# Microcontroller.net
KiCad netlist of a schematic drawn in Altium Designer
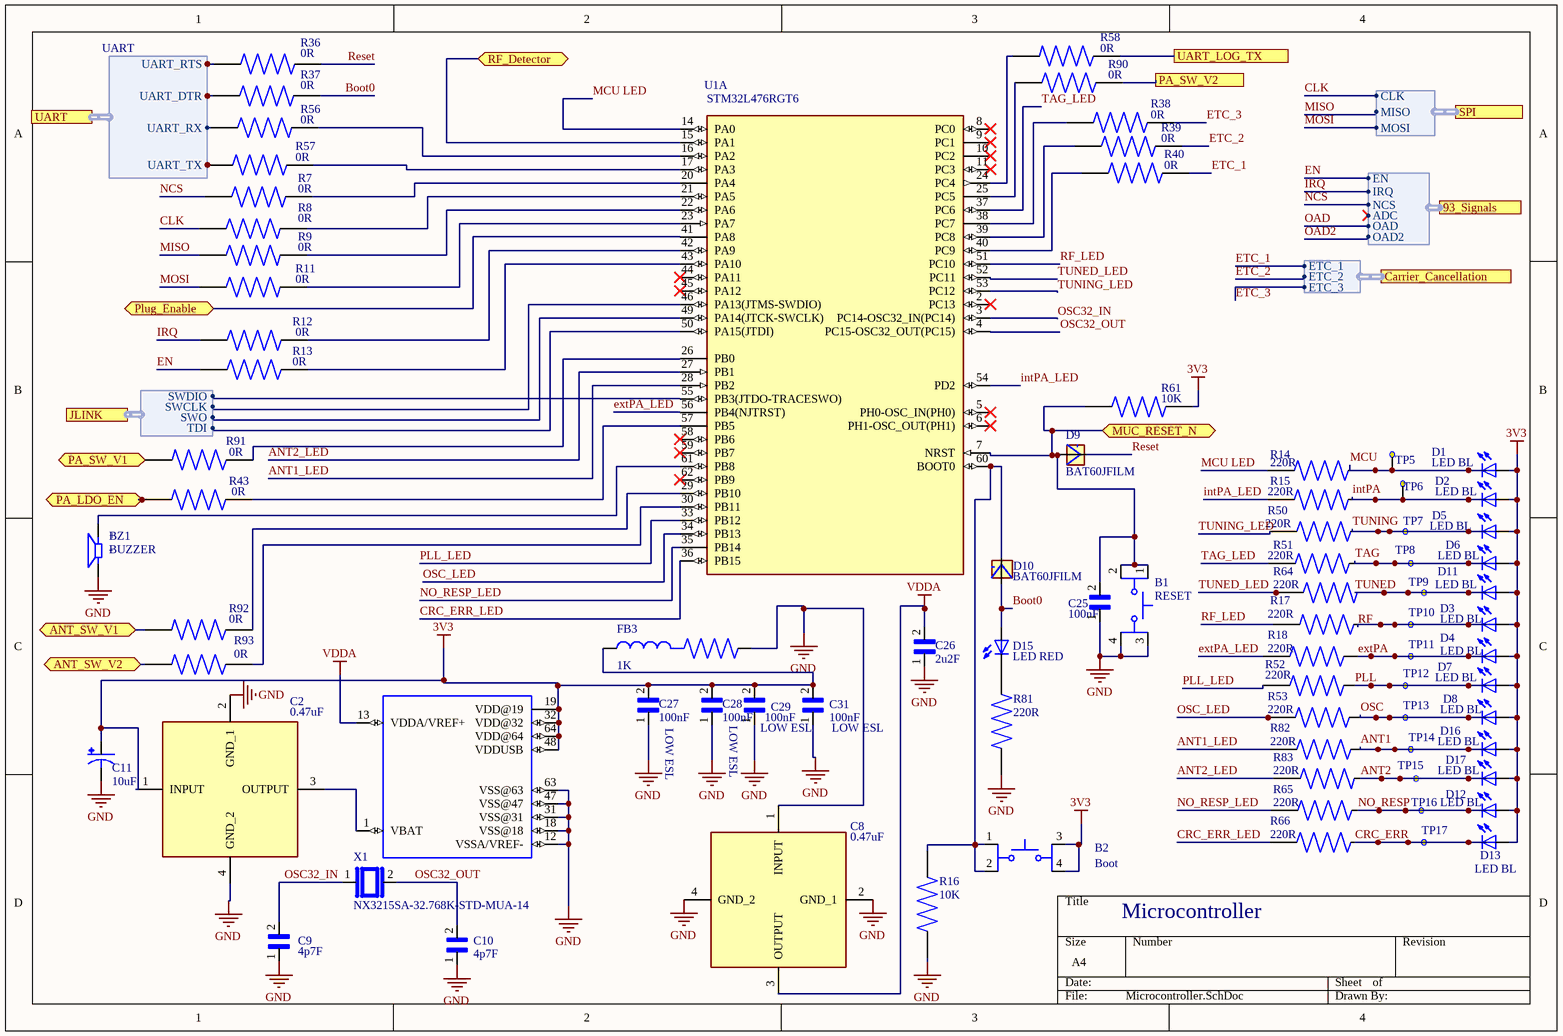
[diagram p0: Microcontroller.SchDoc]

(export (version "E")
  (design (tool "Eeschema 10.0.6"))
  (components
    (comp (ref "B1")
      (value "RESET")
      (footprint "SW_TL3301AF160QG")
      (description "Tactile Switch SPST-NO Top Actuated Surface Mount")
      (fields (field (name "MP") "TL3301AF160QG") (field (name "MF") "E-Switch"))
      (libsource (lib "TL3301AF160QG") (part "TL3301AF160QG"))
    )
    (comp (ref "B2")
      (value "Boot")
      (footprint "SW_TL3301AF160QG")
      (description "Tactile Switch SPST-NO Top Actuated Surface Mount")
      (fields (field (name "MP") "TL3301AF160QG") (field (name "MF") "E-Switch"))
      (libsource (lib "TL3301AF160QG") (part "TL3301AF160QG"))
    )
    (comp (ref "BZ1")
      (value "BUZZER")
      (footprint "SPKR_PKMCS0909E4000-R1")
      (description "Buzzers Transducer, Externally Driven Piezo 1.5V 4kHz 65dB @ 1.5V, 10cm Surface Mount Solder Pads")
      (fields (field (name "DIGI-KEY_PART_NUMBER") "490-9647-1-ND") (field (name "MP") "PKMCS0909E4000-R1"))
      (libsource (lib "PKMCS0909E4000-R1") (part "PKMCS0909E4000-R1"))
    )
    (comp (ref "C2")
      (value "0.47uF")
      (footprint "SamacSys:NFM18CC101R1C3D")
      (description "Capacitor")
      (fields
        (field (name "MANUFACTURER_PART_NUMBER") "NFM18PS474R0J3D")
        (field (name "MOUSER PART NUMBER") "81-NFM18PS474R0J3D")
      )
      (libsource (lib "") (part "NFM18PS474R0J3D_1"))
    )
    (comp (ref "C8")
      (value "0.47uF")
      (footprint "SamacSys:NFM18CC101R1C3D")
      (description "Capacitor")
      (fields
        (field (name "MANUFACTURER_PART_NUMBER") "NFM18PS474R0J3D")
        (field (name "MOUSER PART NUMBER") "81-NFM18PS474R0J3D")
      )
      (libsource (lib "*") (part "NFM18PS474R0J3D"))
    )
    (comp (ref "C9")
      (value "4p7F")
      (footprint "CAPC1005X55N")
      (description "Cap Ceramic 4.7pF 100V C0G 0.25pF SMD 0402 125Â°C Paper T/R")
      (fields (field (name "MP") "GRM1555C2A4R7CA01D"))
      (libsource (lib "GRM1555C2A4R7CA01D") (part "GRM1555C2A4R7CA01D"))
    )
    (comp (ref "C10")
      (value "4p7F")
      (footprint "CAPC1005X55N")
      (description "Cap Ceramic 4.7pF 100V C0G 0.25pF SMD 0402 125Â°C Paper T/R")
      (fields (field (name "MP") "GRM1555C2A4R7CA01D"))
      (libsource (lib "GRM1555C2A4R7CA01D") (part "GRM1555C2A4R7CA01D"))
    )
    (comp (ref "C11")
      (value "10uF")
      (footprint "2917(POL)")
      (description "10 ÂµF 16 V Aluminum - Polymer Capacitors 2917 (7343 Metric) 60mOhm 1000 Hrs @ 105Â°C")
      (fields (field (name "MF") "Murata Electronics") (field (name "MP") "ECASD41C106M060K00"))
      (libsource (lib "ECASD41C106M060K00") (part "ECASD41C106M060K00"))
    )
    (comp (ref "C25")
      (value "100nF")
      (footprint "CAPC1005X55N")
      (description "SMD Capacitor X7R_EIA_ with Capacitance: 0.10uF Tol. 10%. Rated Voltage: 16Vdc")
      (fields (field (name "MF") "Murata") (field (name "MP") "GRM155R71C104KA88D"))
      (libsource (lib "GRM155R71C104KA88D") (part "GRM155R71C104KA88D"))
    )
    (comp (ref "C26")
      (value "2u2F")
      (footprint "CAPC0603X35N")
      (description "SMD Capacitor X5R(EIA) with Capacitance: 2.2uF Tol. 20%. Rated Voltage: 6.3Vdc")
      (fields (field (name "MP") "GRM033R60J225ME15D"))
      (libsource (lib "GRM033R60J225ME15D") (part "GRM033R60J225ME15D"))
    )
    (comp (ref "C27")
      (value "100nF")
      (footprint "CAPC0510X35N")
      (description "SMD Capacitor X6S(EIA) with Capacitance: 0.10uF Tol. 20%. Rated Voltage: 6.3Vdc")
      (fields (field (name "MF") "Murata") (field (name "MP") "LLL153C80J104ME01E"))
      (libsource (lib "LLL153C80J104ME01E") (part "LLL153C80J104ME01E"))
    )
    (comp (ref "C28")
      (value "100nF")
      (footprint "CAPC0510X35N")
      (description "SMD Capacitor X6S(EIA) with Capacitance: 0.10uF Tol. 20%. Rated Voltage: 6.3Vdc")
      (fields (field (name "MF") "Murata") (field (name "MP") "LLL153C80J104ME01E"))
      (libsource (lib "LLL153C80J104ME01E") (part "LLL153C80J104ME01E"))
    )
    (comp (ref "C29")
      (value "100nF")
      (footprint "CAPC0510X35N")
      (description "SMD Capacitor X6S(EIA) with Capacitance: 0.10uF Tol. 20%. Rated Voltage: 6.3Vdc")
      (fields (field (name "MF") "Murata") (field (name "MP") "LLL153C80J104ME01E"))
      (libsource (lib "LLL153C80J104ME01E") (part "LLL153C80J104ME01E"))
    )
    (comp (ref "C31")
      (value "100nF")
      (footprint "CAPC0510X35N")
      (description "SMD Capacitor X6S(EIA) with Capacitance: 0.10uF Tol. 20%. Rated Voltage: 6.3Vdc")
      (fields (field (name "MF") "Murata") (field (name "MP") "LLL153C80J104ME01E"))
      (libsource (lib "LLL153C80J104ME01E") (part "LLL153C80J104ME01E"))
    )
    (comp (ref "D1")
      (value "LED BL")
      (footprint "LED_0402")
      (description "Blue 472nm LED Indication - Discrete 2.9V 0402 (1005 Metric)")
      (fields (field (name "MF") "Panasonic Electronic") (field (name "MP") "LNJ947W8CRA"))
      (libsource (lib "LNJ947W8CRA") (part "LNJ947W8CRA"))
    )
    (comp (ref "D2")
      (value "LED BL")
      (footprint "LED_0402")
      (description "Blue 472nm LED Indication - Discrete 2.9V 0402 (1005 Metric)")
      (fields (field (name "MF") "Panasonic Electronic") (field (name "MP") "LNJ947W8CRA"))
      (libsource (lib "LNJ947W8CRA") (part "LNJ947W8CRA"))
    )
    (comp (ref "D3")
      (value "LED BL")
      (footprint "LED_0402")
      (description "Blue 472nm LED Indication - Discrete 2.9V 0402 (1005 Metric)")
      (fields (field (name "MF") "Panasonic Electronic") (field (name "MP") "LNJ947W8CRA"))
      (libsource (lib "LNJ947W8CRA") (part "LNJ947W8CRA"))
    )
    (comp (ref "D4")
      (value "LED BL")
      (footprint "LED_0402")
      (description "Blue 472nm LED Indication - Discrete 2.9V 0402 (1005 Metric)")
      (fields (field (name "MF") "Panasonic Electronic") (field (name "MP") "LNJ947W8CRA"))
      (libsource (lib "LNJ947W8CRA") (part "LNJ947W8CRA"))
    )
    (comp (ref "D5")
      (value "LED BL")
      (footprint "LED_0402")
      (description "Blue 472nm LED Indication - Discrete 2.9V 0402 (1005 Metric)")
      (fields (field (name "MF") "Panasonic Electronic") (field (name "MP") "LNJ947W8CRA"))
      (libsource (lib "LNJ947W8CRA") (part "LNJ947W8CRA"))
    )
    (comp (ref "D6")
      (value "LED BL")
      (footprint "LED_0402")
      (description "Blue 472nm LED Indication - Discrete 2.9V 0402 (1005 Metric)")
      (fields (field (name "MF") "Panasonic Electronic") (field (name "MP") "LNJ947W8CRA"))
      (libsource (lib "LNJ947W8CRA") (part "LNJ947W8CRA"))
    )
    (comp (ref "D7")
      (value "LED BL")
      (footprint "LED_0402")
      (description "Blue 472nm LED Indication - Discrete 2.9V 0402 (1005 Metric)")
      (fields (field (name "MF") "Panasonic Electronic") (field (name "MP") "LNJ947W8CRA"))
      (libsource (lib "LNJ947W8CRA") (part "LNJ947W8CRA"))
    )
    (comp (ref "D8")
      (value "LED BL")
      (footprint "LED_0402")
      (description "Blue 472nm LED Indication - Discrete 2.9V 0402 (1005 Metric)")
      (fields (field (name "MF") "Panasonic Electronic") (field (name "MP") "LNJ947W8CRA"))
      (libsource (lib "LNJ947W8CRA") (part "LNJ947W8CRA"))
    )
    (comp (ref "D9")
      (value "BAT60JFILM")
      (footprint "SOD323")
      (description "Diode Schottky 10 V 3A (DC) Surface Mount SOD-323")
      (fields (field (name "MF") "STMicroelectronics"))
      (libsource (lib "") (part "BAT60JFILM_1"))
    )
    (comp (ref "D10")
      (value "BAT60JFILM")
      (footprint "SOD323")
      (description "Diode Schottky 10 V 3A (DC) Surface Mount SOD-323")
      (fields (field (name "MF") "STMicroelectronics"))
      (libsource (lib "BAT60JFILM") (part "BAT60JFILM"))
    )
    (comp (ref "D11")
      (value "LED BL")
      (footprint "LED_0402")
      (description "Blue 472nm LED Indication - Discrete 2.9V 0402 (1005 Metric)")
      (fields (field (name "MF") "Panasonic Electronic") (field (name "MP") "LNJ947W8CRA"))
      (libsource (lib "LNJ947W8CRA") (part "LNJ947W8CRA"))
    )
    (comp (ref "D12")
      (value "LED BL")
      (footprint "LED_0402")
      (description "Blue 472nm LED Indication - Discrete 2.9V 0402 (1005 Metric)")
      (fields (field (name "MF") "Panasonic Electronic") (field (name "MP") "LNJ947W8CRA"))
      (libsource (lib "LNJ947W8CRA") (part "LNJ947W8CRA"))
    )
    (comp (ref "D13")
      (value "LED BL")
      (footprint "LED_0402")
      (description "Blue 472nm LED Indication - Discrete 2.9V 0402 (1005 Metric)")
      (fields (field (name "MF") "Panasonic Electronic") (field (name "MP") "LNJ947W8CRA"))
      (libsource (lib "LNJ947W8CRA") (part "LNJ947W8CRA"))
    )
    (comp (ref "D15")
      (value "LED RED")
      (footprint "LED_0402")
      (description "Red 630nm LED Indication - Discrete 1.95V 0402 (1005 Metric)")
      (fields (field (name "MF") "Panasonic Electronic") (field (name "MP") "LNJ247W82RA"))
      (libsource (lib "LNJ247W82RA") (part "LNJ247W82RA"))
    )
    (comp (ref "D16")
      (value "LED BL")
      (footprint "LED_0402")
      (description "Blue 472nm LED Indication - Discrete 2.9V 0402 (1005 Metric)")
      (fields (field (name "MF") "Panasonic Electronic") (field (name "MP") "LNJ947W8CRA"))
      (libsource (lib "LNJ947W8CRA") (part "LNJ947W8CRA"))
    )
    (comp (ref "D17")
      (value "LED BL")
      (footprint "LED_0402")
      (description "Blue 472nm LED Indication - Discrete 2.9V 0402 (1005 Metric)")
      (fields (field (name "MF") "Panasonic Electronic") (field (name "MP") "LNJ947W8CRA"))
      (libsource (lib "LNJ947W8CRA") (part "LNJ947W8CRA"))
    )
    (comp (ref "FB3")
      (value "1K")
      (footprint "BEADC1005X55N")
      (description "1 kOhms @ 100MHz 1 Signal Line Ferrite Bead 0402 _1005 Metric_ 250mA 1.1Ohm")
      (fields (field (name "MF") "Murata") (field (name "DIGI-KEY_PART_NUMBER") "490-3999-1-ND"))
      (libsource (lib "BLM15HG102SN1D") (part "BLM15HG102SN1D"))
    )
    (comp (ref "R7")
      (value "0R")
      (footprint "RESC1005X37N")
      (fields (field (name "MF") "{'manufacturer': u'YAGEO'}") (field (name "MP") "RC0402JR-070RL"))
      (libsource (lib "RC0402JR-070RL") (part "RC0402JR-070RL"))
    )
    (comp (ref "R8")
      (value "0R")
      (footprint "RESC1005X37N")
      (fields (field (name "MF") "{'manufacturer': u'YAGEO'}") (field (name "MP") "RC0402JR-070RL"))
      (libsource (lib "RC0402JR-070RL") (part "RC0402JR-070RL"))
    )
    (comp (ref "R9")
      (value "0R")
      (footprint "RESC1005X37N")
      (fields (field (name "MF") "{'manufacturer': u'YAGEO'}") (field (name "MP") "RC0402JR-070RL"))
      (libsource (lib "RC0402JR-070RL") (part "RC0402JR-070RL"))
    )
    (comp (ref "R11")
      (value "0R")
      (footprint "RESC1005X37N")
      (fields (field (name "MF") "{'manufacturer': u'YAGEO'}") (field (name "MP") "RC0402JR-070RL"))
      (libsource (lib "RC0402JR-070RL") (part "RC0402JR-070RL"))
    )
    (comp (ref "R12")
      (value "0R")
      (footprint "RESC1005X37N")
      (fields (field (name "MF") "{'manufacturer': u'YAGEO'}") (field (name "MP") "RC0402JR-070RL"))
      (libsource (lib "RC0402JR-070RL") (part "RC0402JR-070RL"))
    )
    (comp (ref "R13")
      (value "0R")
      (footprint "RESC1005X37N")
      (fields (field (name "MF") "{'manufacturer': u'YAGEO'}") (field (name "MP") "RC0402JR-070RL"))
      (libsource (lib "RC0402JR-070RL") (part "RC0402JR-070RL"))
    )
    (comp (ref "R14")
      (value "220R")
      (footprint "RESC1005X40N")
      (description "220 Ohms ±5% 0.063W, 1/16W Chip Resistor 0402 (1005 Metric) Moisture Resistant Thick Film")
      (fields (field (name "MF") "Yageo") (field (name "MP") "RC0402JR-07220RL"))
      (libsource (lib "RC0402JR-07220RL") (part "RC0402JR-07220RL"))
    )
    (comp (ref "R15")
      (value "220R")
      (footprint "RESC1005X40N")
      (description "220 Ohms ±5% 0.063W, 1/16W Chip Resistor 0402 (1005 Metric) Moisture Resistant Thick Film")
      (fields (field (name "MF") "Yageo") (field (name "MP") "RC0402JR-07220RL"))
      (libsource (lib "RC0402JR-07220RL") (part "RC0402JR-07220RL"))
    )
    (comp (ref "R16")
      (value "10K")
      (footprint "RESC1005X40N")
      (description "10 kOhms Â±1% 0.063W, 1/16W Chip Resistor 0402 (1005 Metric) Moisture Resistant Thick Film")
      (fields (field (name "MF") "Yageo") (field (name "MP") "RC0402FR-0710KL"))
      (libsource (lib "RC0402FR-0710KL") (part "RC0402FR-0710KL"))
    )
    (comp (ref "R17")
      (value "220R")
      (footprint "RESC1005X40N")
      (description "220 Ohms ±5% 0.063W, 1/16W Chip Resistor 0402 (1005 Metric) Moisture Resistant Thick Film")
      (fields (field (name "MF") "Yageo") (field (name "MP") "RC0402JR-07220RL"))
      (libsource (lib "RC0402JR-07220RL") (part "RC0402JR-07220RL"))
    )
    (comp (ref "R18")
      (value "220R")
      (footprint "RESC1005X40N")
      (description "220 Ohms ±5% 0.063W, 1/16W Chip Resistor 0402 (1005 Metric) Moisture Resistant Thick Film")
      (fields (field (name "MF") "Yageo") (field (name "MP") "RC0402JR-07220RL"))
      (libsource (lib "RC0402JR-07220RL") (part "RC0402JR-07220RL"))
    )
    (comp (ref "R36")
      (value "0R")
      (footprint "RESC1005X37N")
      (fields (field (name "MF") "{'manufacturer': u'YAGEO'}") (field (name "MP") "RC0402JR-070RL"))
      (libsource (lib "RC0402JR-070RL") (part "RC0402JR-070RL"))
    )
    (comp (ref "R37")
      (value "0R")
      (footprint "RESC1005X37N")
      (fields (field (name "MF") "{'manufacturer': u'YAGEO'}") (field (name "MP") "RC0402JR-070RL"))
      (libsource (lib "RC0402JR-070RL") (part "RC0402JR-070RL"))
    )
    (comp (ref "R38")
      (value "0R")
      (footprint "RESC1005X37N")
      (fields (field (name "MF") "{'manufacturer': u'YAGEO'}") (field (name "MP") "RC0402JR-070RL"))
      (libsource (lib "RC0402JR-070RL") (part "RC0402JR-070RL"))
    )
    (comp (ref "R39")
      (value "0R")
      (footprint "RESC1005X37N")
      (fields (field (name "MF") "{'manufacturer': u'YAGEO'}") (field (name "MP") "RC0402JR-070RL"))
      (libsource (lib "RC0402JR-070RL") (part "RC0402JR-070RL"))
    )
    (comp (ref "R40")
      (value "0R")
      (footprint "RESC1005X37N")
      (fields (field (name "MF") "{'manufacturer': u'YAGEO'}") (field (name "MP") "RC0402JR-070RL"))
      (libsource (lib "RC0402JR-070RL") (part "RC0402JR-070RL"))
    )
    (comp (ref "R43")
      (value "0R")
      (footprint "RESC1005X37N")
      (fields (field (name "MF") "{'manufacturer': u'YAGEO'}") (field (name "MP") "RC0402JR-070RL"))
      (libsource (lib "RC0402JR-070RL") (part "RC0402JR-070RL"))
    )
    (comp (ref "R50")
      (value "220R")
      (footprint "RESC1005X40N")
      (description "220 Ohms ±5% 0.063W, 1/16W Chip Resistor 0402 (1005 Metric) Moisture Resistant Thick Film")
      (fields (field (name "MF") "Yageo") (field (name "MP") "RC0402JR-07220RL"))
      (libsource (lib "RC0402JR-07220RL") (part "RC0402JR-07220RL"))
    )
    (comp (ref "R51")
      (value "220R")
      (footprint "RESC1005X40N")
      (description "220 Ohms ±5% 0.063W, 1/16W Chip Resistor 0402 (1005 Metric) Moisture Resistant Thick Film")
      (fields (field (name "MF") "Yageo") (field (name "MP") "RC0402JR-07220RL"))
      (libsource (lib "RC0402JR-07220RL") (part "RC0402JR-07220RL"))
    )
    (comp (ref "R52")
      (value "220R")
      (footprint "RESC1005X40N")
      (description "220 Ohms ±5% 0.063W, 1/16W Chip Resistor 0402 (1005 Metric) Moisture Resistant Thick Film")
      (fields (field (name "MF") "Yageo") (field (name "MP") "RC0402JR-07220RL"))
      (libsource (lib "RC0402JR-07220RL") (part "RC0402JR-07220RL"))
    )
    (comp (ref "R53")
      (value "220R")
      (footprint "RESC1005X40N")
      (description "220 Ohms ±5% 0.063W, 1/16W Chip Resistor 0402 (1005 Metric) Moisture Resistant Thick Film")
      (fields (field (name "MF") "Yageo") (field (name "MP") "RC0402JR-07220RL"))
      (libsource (lib "RC0402JR-07220RL") (part "RC0402JR-07220RL"))
    )
    (comp (ref "R56")
      (value "0R")
      (footprint "RESC1005X37N")
      (fields (field (name "MF") "{'manufacturer': u'YAGEO'}") (field (name "MP") "RC0402JR-070RL"))
      (libsource (lib "RC0402JR-070RL") (part "RC0402JR-070RL"))
    )
    (comp (ref "R57")
      (value "0R")
      (footprint "RESC1005X37N")
      (fields (field (name "MF") "{'manufacturer': u'YAGEO'}") (field (name "MP") "RC0402JR-070RL"))
      (libsource (lib "RC0402JR-070RL") (part "RC0402JR-070RL"))
    )
    (comp (ref "R58")
      (value "0R")
      (footprint "RESC1005X37N")
      (fields (field (name "MF") "{'manufacturer': u'YAGEO'}") (field (name "MP") "RC0402JR-070RL"))
      (libsource (lib "RC0402JR-070RL") (part "RC0402JR-070RL"))
    )
    (comp (ref "R61")
      (value "10K")
      (footprint "RESC1005X40N")
      (description "10 kOhms Â±1% 0.063W, 1/16W Chip Resistor 0402 (1005 Metric) Moisture Resistant Thick Film")
      (fields (field (name "MF") "Yageo") (field (name "MP") "RC0402FR-0710KL"))
      (libsource (lib "RC0402FR-0710KL") (part "RC0402FR-0710KL"))
    )
    (comp (ref "R64")
      (value "220R")
      (footprint "RESC1005X40N")
      (description "220 Ohms ±5% 0.063W, 1/16W Chip Resistor 0402 (1005 Metric) Moisture Resistant Thick Film")
      (fields (field (name "MF") "Yageo") (field (name "MP") "RC0402JR-07220RL"))
      (libsource (lib "RC0402JR-07220RL") (part "RC0402JR-07220RL"))
    )
    (comp (ref "R65")
      (value "220R")
      (footprint "RESC1005X40N")
      (description "220 Ohms ±5% 0.063W, 1/16W Chip Resistor 0402 (1005 Metric) Moisture Resistant Thick Film")
      (fields (field (name "MF") "Yageo") (field (name "MP") "RC0402JR-07220RL"))
      (libsource (lib "RC0402JR-07220RL") (part "RC0402JR-07220RL"))
    )
    (comp (ref "R66")
      (value "220R")
      (footprint "RESC1005X40N")
      (description "220 Ohms ±5% 0.063W, 1/16W Chip Resistor 0402 (1005 Metric) Moisture Resistant Thick Film")
      (fields (field (name "MF") "Yageo") (field (name "MP") "RC0402JR-07220RL"))
      (libsource (lib "RC0402JR-07220RL") (part "RC0402JR-07220RL"))
    )
    (comp (ref "R81")
      (value "220R")
      (footprint "RESC1005X40N")
      (description "220 Ohms ±5% 0.063W, 1/16W Chip Resistor 0402 (1005 Metric) Moisture Resistant Thick Film")
      (fields (field (name "MF") "Yageo") (field (name "MP") "RC0402JR-07220RL"))
      (libsource (lib "RC0402JR-07220RL") (part "RC0402JR-07220RL"))
    )
    (comp (ref "R82")
      (value "220R")
      (footprint "RESC1005X40N")
      (description "220 Ohms ±5% 0.063W, 1/16W Chip Resistor 0402 (1005 Metric) Moisture Resistant Thick Film")
      (fields (field (name "MF") "Yageo") (field (name "MP") "RC0402JR-07220RL"))
      (libsource (lib "RC0402JR-07220RL") (part "RC0402JR-07220RL"))
    )
    (comp (ref "R83")
      (value "220R")
      (footprint "RESC1005X40N")
      (description "220 Ohms ±5% 0.063W, 1/16W Chip Resistor 0402 (1005 Metric) Moisture Resistant Thick Film")
      (fields (field (name "MF") "Yageo") (field (name "MP") "RC0402JR-07220RL"))
      (libsource (lib "RC0402JR-07220RL") (part "RC0402JR-07220RL"))
    )
    (comp (ref "R90")
      (value "0R")
      (footprint "RESC1005X37N")
      (fields (field (name "MF") "{'manufacturer': u'YAGEO'}") (field (name "MP") "RC0402JR-070RL"))
      (libsource (lib "RC0402JR-070RL") (part "RC0402JR-070RL"))
    )
    (comp (ref "R91")
      (value "0R")
      (footprint "RESC1005X37N")
      (fields (field (name "MF") "{'manufacturer': u'YAGEO'}") (field (name "MP") "RC0402JR-070RL"))
      (libsource (lib "RC0402JR-070RL") (part "RC0402JR-070RL"))
    )
    (comp (ref "R92")
      (value "0R")
      (footprint "RESC1005X37N")
      (fields (field (name "MF") "{'manufacturer': u'YAGEO'}") (field (name "MP") "RC0402JR-070RL"))
      (libsource (lib "RC0402JR-070RL") (part "RC0402JR-070RL"))
    )
    (comp (ref "R93")
      (value "0R")
      (footprint "RESC1005X37N")
      (fields (field (name "MF") "{'manufacturer': u'YAGEO'}") (field (name "MP") "RC0402JR-070RL"))
      (libsource (lib "RC0402JR-070RL") (part "RC0402JR-070RL"))
    )
    (comp (ref "TP5")
      (value "Testpoint")
      (footprint "Testpoint_FP")
      (libsource (lib "Schlib2") (part "Testpoint"))
    )
    (comp (ref "TP6")
      (value "Testpoint")
      (footprint "Testpoint_FP")
      (libsource (lib "Schlib2") (part "Testpoint"))
    )
    (comp (ref "TP7")
      (value "Testpoint")
      (footprint "Testpoint_FP")
      (libsource (lib "Schlib2") (part "Testpoint"))
    )
    (comp (ref "TP8")
      (value "Testpoint")
      (footprint "Testpoint_FP")
      (libsource (lib "Schlib2") (part "Testpoint"))
    )
    (comp (ref "TP9")
      (value "Testpoint")
      (footprint "Testpoint_FP")
      (libsource (lib "Schlib2") (part "Testpoint"))
    )
    (comp (ref "TP10")
      (value "Testpoint")
      (footprint "Testpoint_FP")
      (libsource (lib "Schlib2") (part "Testpoint"))
    )
    (comp (ref "TP11")
      (value "Testpoint")
      (footprint "Testpoint_FP")
      (libsource (lib "Schlib2") (part "Testpoint"))
    )
    (comp (ref "TP12")
      (value "Testpoint")
      (footprint "Testpoint_FP")
      (libsource (lib "Schlib2") (part "Testpoint"))
    )
    (comp (ref "TP13")
      (value "Testpoint")
      (footprint "Testpoint_FP")
      (libsource (lib "Schlib2") (part "Testpoint"))
    )
    (comp (ref "TP14")
      (value "Testpoint")
      (footprint "Testpoint_FP")
      (libsource (lib "Schlib2") (part "Testpoint"))
    )
    (comp (ref "TP15")
      (value "Testpoint")
      (footprint "Testpoint_FP")
      (libsource (lib "Schlib2") (part "Testpoint"))
    )
    (comp (ref "TP16")
      (value "Testpoint")
      (footprint "Testpoint_FP")
      (libsource (lib "Schlib2") (part "Testpoint"))
    )
    (comp (ref "TP17")
      (value "Testpoint")
      (footprint "Testpoint_FP")
      (libsource (lib "Schlib2") (part "Testpoint"))
    )
    (comp (ref "U1A")
      (value "STM32L476RGT6")
      (footprint "LQFP-64(10X10)MM")
      (fields (field (name "MF") "STMicroelectronics"))
      (libsource (lib "STM32L476RGT6") (part "STM32L476RGT6"))
    )
    (comp (ref "X1")
      (value "NX3215SA-32.768K-STD-MUA-14")
      (footprint "XTAL_NX3215SA-32.768K-STD-MUA-14")
      (description "32.768 kHz Â±20ppm Crystal 6pF 70 kOhms 2-SMD, No Lead")
      (fields (field (name "MF") "NDK America,"))
      (libsource (lib "NX3215SA-32.768K-STD-MUA-14") (part "NX3215SA-32.768K-STD-MUA-14"))
    )
  )
  (nets
    (net (code "7") (name "/ANT1") (class "Default")
      (node (ref "D16") (pin "C") (pinfunction "C_C") (pintype "passive"))
      (node (ref "R82") (pin "2") (pinfunction "2_2") (pintype "passive"))
      (node (ref "TP14") (pin "TP?") (pinfunction "Testpoint_TP?") (pintype "passive"))
    )
    (net (code "8") (name "/ANT1_LED") (class "Default")
      (node (ref "R82") (pin "1") (pinfunction "1_1") (pintype "passive"))
      (node (ref "U1A") (pin "28") (pinfunction "PB2_28") (pintype "input"))
    )
    (net (code "9") (name "/ANT2") (class "Default")
      (node (ref "D17") (pin "C") (pinfunction "C_C") (pintype "passive"))
      (node (ref "R83") (pin "2") (pinfunction "2_2") (pintype "passive"))
      (node (ref "TP15") (pin "TP?") (pinfunction "Testpoint_TP?") (pintype "passive"))
    )
    (net (code "10") (name "/ANT2_LED") (class "Default")
      (node (ref "R83") (pin "1") (pinfunction "1_1") (pintype "passive"))
      (node (ref "U1A") (pin "27") (pinfunction "PB1_27") (pintype "input"))
    )
    (net (code "11") (name "/ANT_SW_V1") (class "Default")
      (node (ref "R92") (pin "1") (pinfunction "1_1") (pintype "passive"))
    )
    (net (code "12") (name "/ANT_SW_V2") (class "Default")
      (node (ref "R93") (pin "1") (pinfunction "1_1") (pintype "passive"))
    )
    (net (code "13") (name "/Boot0") (class "Default")
      (node (ref "D10") (pin "A") (pinfunction "A_A") (pintype "passive"))
      (node (ref "D15") (pin "A") (pinfunction "A_A") (pintype "passive"))
      (node (ref "R37") (pin "2") (pinfunction "2_2") (pintype "passive"))
    )
    (net (code "14") (name "/CLK") (class "Default")
      (node (ref "R8") (pin "1") (pinfunction "1_1") (pintype "passive"))
    )
    (net (code "15") (name "/CRC_ERR") (class "Default")
      (node (ref "D13") (pin "C") (pinfunction "C_C") (pintype "passive"))
      (node (ref "R66") (pin "2") (pinfunction "2_2") (pintype "passive"))
      (node (ref "TP17") (pin "TP?") (pinfunction "Testpoint_TP?") (pintype "passive"))
    )
    (net (code "16") (name "/CRC_ERR_LED") (class "Default")
      (node (ref "R66") (pin "1") (pinfunction "1_1") (pintype "passive"))
      (node (ref "U1A") (pin "36") (pinfunction "PB15_36") (pintype "bidirectional"))
    )
    (net (code "17") (name "/EN") (class "Default")
      (node (ref "R13") (pin "1") (pinfunction "1_1") (pintype "passive"))
    )
    (net (code "18") (name "/ETC_1") (class "Default")
      (node (ref "R40") (pin "2") (pinfunction "2_2") (pintype "passive"))
    )
    (net (code "19") (name "/ETC_2") (class "Default")
      (node (ref "R39") (pin "2") (pinfunction "2_2") (pintype "passive"))
    )
    (net (code "20") (name "/ETC_3") (class "Default")
      (node (ref "R38") (pin "2") (pinfunction "2_2") (pintype "passive"))
    )
    (net (code "21") (name "/IRQ") (class "Default")
      (node (ref "R12") (pin "1") (pinfunction "1_1") (pintype "passive"))
    )
    (net (code "22") (name "/MCU") (class "Default")
      (node (ref "D1") (pin "C") (pinfunction "C_C") (pintype "passive"))
      (node (ref "R14") (pin "2") (pinfunction "2_2") (pintype "passive"))
      (node (ref "TP5") (pin "TP?") (pinfunction "Testpoint_TP?") (pintype "passive"))
    )
    (net (code "23") (name "/MCU LED") (class "Default")
      (node (ref "R14") (pin "1") (pinfunction "1_1") (pintype "passive"))
      (node (ref "U1A") (pin "14") (pinfunction "PA0_14") (pintype "bidirectional"))
    )
    (net (code "24") (name "/MISO") (class "Default")
      (node (ref "R9") (pin "1") (pinfunction "1_1") (pintype "passive"))
    )
    (net (code "25") (name "/MOSI") (class "Default")
      (node (ref "R11") (pin "1") (pinfunction "1_1") (pintype "passive"))
    )
    (net (code "26") (name "/MUC_RESET_N") (class "Default")
      (node (ref "B1") (pin "1") (pinfunction "1_1") (pintype "passive"))
      (node (ref "B1") (pin "2") (pinfunction "2_2") (pintype "passive"))
      (node (ref "C25") (pin "2") (pinfunction "2_2") (pintype "passive"))
      (node (ref "D9") (pin "A") (pinfunction "A_A") (pintype "passive"))
      (node (ref "R61") (pin "1") (pinfunction "1_1") (pintype "passive"))
      (node (ref "U1A") (pin "7") (pinfunction "NRST_7") (pintype "input"))
    )
    (net (code "27") (name "/NCS") (class "Default")
      (node (ref "R7") (pin "1") (pinfunction "1_1") (pintype "passive"))
    )
    (net (code "28") (name "/NO_RESP") (class "Default")
      (node (ref "D12") (pin "C") (pinfunction "C_C") (pintype "passive"))
      (node (ref "R65") (pin "2") (pinfunction "2_2") (pintype "passive"))
      (node (ref "TP16") (pin "TP?") (pinfunction "Testpoint_TP?") (pintype "passive"))
    )
    (net (code "29") (name "/NO_RESP_LED") (class "Default")
      (node (ref "R65") (pin "1") (pinfunction "1_1") (pintype "passive"))
      (node (ref "U1A") (pin "35") (pinfunction "PB14_35") (pintype "passive"))
    )
    (net (code "32") (name "/OSC") (class "Default")
      (node (ref "D8") (pin "C") (pinfunction "C_C") (pintype "passive"))
      (node (ref "R53") (pin "2") (pinfunction "2_2") (pintype "passive"))
      (node (ref "TP13") (pin "TP?") (pinfunction "Testpoint_TP?") (pintype "passive"))
    )
    (net (code "33") (name "/OSC32_IN") (class "Default")
      (node (ref "C9") (pin "2") (pinfunction "2_2") (pintype "passive"))
      (node (ref "U1A") (pin "3") (pinfunction "PC14-OSC32_IN(PC14)_3") (pintype "bidirectional"))
      (node (ref "X1") (pin "1") (pinfunction "1_1") (pintype "passive"))
    )
    (net (code "34") (name "/OSC32_OUT") (class "Default")
      (node (ref "C10") (pin "2") (pinfunction "2_2") (pintype "passive"))
      (node (ref "U1A") (pin "4") (pinfunction "PC15-OSC32_OUT(PC15)_4") (pintype "bidirectional"))
      (node (ref "X1") (pin "2") (pinfunction "2_2") (pintype "passive"))
    )
    (net (code "35") (name "/OSC_LED") (class "Default")
      (node (ref "R53") (pin "1") (pinfunction "1_1") (pintype "passive"))
      (node (ref "U1A") (pin "34") (pinfunction "PB13_34") (pintype "bidirectional"))
    )
    (net (code "36") (name "/PA_LDO_EN") (class "Default")
      (node (ref "R43") (pin "1") (pinfunction "1_1") (pintype "passive"))
    )
    (net (code "37") (name "/PA_SW_V1") (class "Default")
      (node (ref "R91") (pin "1") (pinfunction "1_1") (pintype "passive"))
    )
    (net (code "38") (name "/PA_SW_V2") (class "Default")
      (node (ref "R90") (pin "2") (pinfunction "2_2") (pintype "passive"))
    )
    (net (code "39") (name "/PLL") (class "Default")
      (node (ref "D7") (pin "C") (pinfunction "C_C") (pintype "passive"))
      (node (ref "R52") (pin "2") (pinfunction "2_2") (pintype "passive"))
      (node (ref "TP12") (pin "TP?") (pinfunction "Testpoint_TP?") (pintype "passive"))
    )
    (net (code "40") (name "/PLL_LED") (class "Default")
      (node (ref "R52") (pin "1") (pinfunction "1_1") (pintype "passive"))
      (node (ref "U1A") (pin "33") (pinfunction "PB12_33") (pintype "bidirectional"))
    )
    (net (code "41") (name "/Plug_Enable") (class "Default")
      (node (ref "U1A") (pin "41") (pinfunction "PA8_41") (pintype "power_in"))
    )
    (net (code "42") (name "/RF") (class "Default")
      (node (ref "D3") (pin "C") (pinfunction "C_C") (pintype "passive"))
      (node (ref "R17") (pin "2") (pinfunction "2_2") (pintype "passive"))
      (node (ref "TP10") (pin "TP?") (pinfunction "Testpoint_TP?") (pintype "passive"))
    )
    (net (code "43") (name "/RF_Detector") (class "Default")
      (node (ref "U1A") (pin "15") (pinfunction "PA1_15") (pintype "bidirectional"))
    )
    (net (code "44") (name "/RF_LED") (class "Default")
      (node (ref "R17") (pin "1") (pinfunction "1_1") (pintype "passive"))
      (node (ref "U1A") (pin "51") (pinfunction "PC10_51") (pintype "bidirectional"))
    )
    (net (code "45") (name "/Reset") (class "Default")
      (node (ref "D9") (pin "C") (pinfunction "C_C") (pintype "passive"))
      (node (ref "R36") (pin "2") (pinfunction "2_2") (pintype "passive"))
    )
    (net (code "46") (name "/SWCLK") (class "Default")
      (node (ref "U1A") (pin "46") (pinfunction "PA13(JTMS-SWDIO)_46") (pintype "bidirectional"))
    )
    (net (code "47") (name "/SWDIO") (class "Default")
      (node (ref "U1A") (pin "55") (pinfunction "PB3(JTDO-TRACESWO)_55") (pintype "bidirectional"))
    )
    (net (code "48") (name "/SWO") (class "Default")
      (node (ref "U1A") (pin "49") (pinfunction "PA14(JTCK-SWCLK)_49") (pintype "bidirectional"))
    )
    (net (code "49") (name "/TAG") (class "Default")
      (node (ref "D6") (pin "C") (pinfunction "C_C") (pintype "passive"))
      (node (ref "R51") (pin "2") (pinfunction "2_2") (pintype "passive"))
      (node (ref "TP8") (pin "TP?") (pinfunction "Testpoint_TP?") (pintype "passive"))
    )
    (net (code "50") (name "/TAG_LED") (class "Default")
      (node (ref "R51") (pin "1") (pinfunction "1_1") (pintype "passive"))
      (node (ref "U1A") (pin "37") (pinfunction "PC6_37") (pintype "bidirectional"))
    )
    (net (code "51") (name "/TDI") (class "Default")
      (node (ref "U1A") (pin "50") (pinfunction "PA15(JTDI)_50") (pintype "bidirectional"))
    )
    (net (code "52") (name "/TUNED") (class "Default")
      (node (ref "D11") (pin "C") (pinfunction "C_C") (pintype "passive"))
      (node (ref "R64") (pin "2") (pinfunction "2_2") (pintype "passive"))
      (node (ref "TP9") (pin "TP?") (pinfunction "Testpoint_TP?") (pintype "passive"))
    )
    (net (code "53") (name "/TUNED_LED") (class "Default")
      (node (ref "R64") (pin "1") (pinfunction "1_1") (pintype "passive"))
      (node (ref "U1A") (pin "52") (pinfunction "PC11_52") (pintype "bidirectional"))
    )
    (net (code "54") (name "/TUNING") (class "Default")
      (node (ref "D5") (pin "C") (pinfunction "C_C") (pintype "passive"))
      (node (ref "R50") (pin "2") (pinfunction "2_2") (pintype "passive"))
      (node (ref "TP7") (pin "TP?") (pinfunction "Testpoint_TP?") (pintype "passive"))
    )
    (net (code "55") (name "/TUNING_LED") (class "Default")
      (node (ref "R50") (pin "1") (pinfunction "1_1") (pintype "passive"))
      (node (ref "U1A") (pin "53") (pinfunction "PC12_53") (pintype "bidirectional"))
    )
    (net (code "56") (name "/UART_DTR") (class "Default")
      (node (ref "R37") (pin "1") (pinfunction "1_1") (pintype "passive"))
    )
    (net (code "57") (name "/UART_LOG_TX") (class "Default")
      (node (ref "R58") (pin "2") (pinfunction "2_2") (pintype "passive"))
    )
    (net (code "58") (name "/UART_RTS") (class "Default")
      (node (ref "R36") (pin "1") (pinfunction "1_1") (pintype "passive"))
    )
    (net (code "59") (name "/UART_RX") (class "Default")
      (node (ref "R56") (pin "1") (pinfunction "1_1") (pintype "passive"))
    )
    (net (code "60") (name "/UART_TX") (class "Default")
      (node (ref "R57") (pin "1") (pinfunction "1_1") (pintype "passive"))
    )
    (net (code "61") (name "/extPA") (class "Default")
      (node (ref "D4") (pin "C") (pinfunction "C_C") (pintype "passive"))
      (node (ref "R18") (pin "2") (pinfunction "2_2") (pintype "passive"))
      (node (ref "TP11") (pin "TP?") (pinfunction "Testpoint_TP?") (pintype "passive"))
    )
    (net (code "62") (name "/extPA_LED") (class "Default")
      (node (ref "R18") (pin "1") (pinfunction "1_1") (pintype "passive"))
      (node (ref "U1A") (pin "56") (pinfunction "PB4(NJTRST)_56") (pintype "power_in"))
    )
    (net (code "63") (name "/intPA") (class "Default")
      (node (ref "D2") (pin "C") (pinfunction "C_C") (pintype "passive"))
      (node (ref "R15") (pin "2") (pinfunction "2_2") (pintype "passive"))
      (node (ref "TP6") (pin "TP?") (pinfunction "Testpoint_TP?") (pintype "passive"))
    )
    (net (code "64") (name "/intPA_LED") (class "Default")
      (node (ref "R15") (pin "1") (pinfunction "1_1") (pintype "passive"))
      (node (ref "U1A") (pin "54") (pinfunction "PD2_54") (pintype "bidirectional"))
    )
    (net (code "70") (name "3V3") (class "Default")
      (node (ref "B2") (pin "3") (pinfunction "3_3") (pintype "passive"))
      (node (ref "B2") (pin "4") (pinfunction "4_4") (pintype "passive"))
      (node (ref "C11") (pin "1") (pinfunction "POS_1") (pintype "passive"))
      (node (ref "C2") (pin "1") (pinfunction "INPUT_1") (pintype "passive"))
      (node (ref "C27") (pin "2") (pinfunction "2_2") (pintype "passive"))
      (node (ref "C28") (pin "2") (pinfunction "2_2") (pintype "passive"))
      (node (ref "C29") (pin "2") (pinfunction "2_2") (pintype "passive"))
      (node (ref "C31") (pin "2") (pinfunction "2_2") (pintype "passive"))
      (node (ref "D1") (pin "A") (pinfunction "A_A") (pintype "passive"))
      (node (ref "D11") (pin "A") (pinfunction "A_A") (pintype "passive"))
      (node (ref "D12") (pin "A") (pinfunction "A_A") (pintype "passive"))
      (node (ref "D13") (pin "A") (pinfunction "A_A") (pintype "passive"))
      (node (ref "D16") (pin "A") (pinfunction "A_A") (pintype "passive"))
      (node (ref "D17") (pin "A") (pinfunction "A_A") (pintype "passive"))
      (node (ref "D2") (pin "A") (pinfunction "A_A") (pintype "passive"))
      (node (ref "D3") (pin "A") (pinfunction "A_A") (pintype "passive"))
      (node (ref "D4") (pin "A") (pinfunction "A_A") (pintype "passive"))
      (node (ref "D5") (pin "A") (pinfunction "A_A") (pintype "passive"))
      (node (ref "D6") (pin "A") (pinfunction "A_A") (pintype "passive"))
      (node (ref "D7") (pin "A") (pinfunction "A_A") (pintype "passive"))
      (node (ref "D8") (pin "A") (pinfunction "A_A") (pintype "passive"))
      (node (ref "FB3") (pin "1") (pinfunction "1_1") (pintype "passive"))
      (node (ref "R61") (pin "2") (pinfunction "2_2") (pintype "passive"))
      (node (ref "U1A") (pin "19") (pinfunction "VDD@19_19") (pintype "power_in"))
      (node (ref "U1A") (pin "32") (pinfunction "VDD@32_32") (pintype "bidirectional"))
      (node (ref "U1A") (pin "48") (pinfunction "VDDUSB_48") (pintype "bidirectional"))
      (node (ref "U1A") (pin "64") (pinfunction "VDD@64_64") (pintype "bidirectional"))
    )
    (net (code "71") (name "GND") (class "Default")
      (node (ref "B1") (pin "3") (pinfunction "3_3") (pintype "passive"))
      (node (ref "B1") (pin "4") (pinfunction "4_4") (pintype "passive"))
      (node (ref "BZ1") (pin "2") (pinfunction "N_2") (pintype "passive"))
      (node (ref "C10") (pin "1") (pinfunction "1_1") (pintype "passive"))
      (node (ref "C11") (pin "2") (pinfunction "NEG_2") (pintype "passive"))
      (node (ref "C2") (pin "2") (pinfunction "GND_1_2") (pintype "passive"))
      (node (ref "C2") (pin "4") (pinfunction "GND_2_4") (pintype "passive"))
      (node (ref "C25") (pin "1") (pinfunction "1_1") (pintype "passive"))
      (node (ref "C26") (pin "1") (pinfunction "1_1") (pintype "passive"))
      (node (ref "C27") (pin "1") (pinfunction "1_1") (pintype "passive"))
      (node (ref "C28") (pin "1") (pinfunction "1_1") (pintype "passive"))
      (node (ref "C29") (pin "1") (pinfunction "1_1") (pintype "passive"))
      (node (ref "C31") (pin "1") (pinfunction "1_1") (pintype "passive"))
      (node (ref "C8") (pin "1") (pinfunction "INPUT_1") (pintype "passive"))
      (node (ref "C8") (pin "2") (pinfunction "GND_1_2") (pintype "passive"))
      (node (ref "C8") (pin "4") (pinfunction "GND_2_4") (pintype "passive"))
      (node (ref "C9") (pin "1") (pinfunction "1_1") (pintype "passive"))
      (node (ref "FB3") (pin "2") (pinfunction "2_2") (pintype "passive"))
      (node (ref "R16") (pin "1") (pinfunction "1_1") (pintype "passive"))
      (node (ref "R81") (pin "1") (pinfunction "1_1") (pintype "passive"))
      (node (ref "U1A") (pin "12") (pinfunction "VSSA/VREF-_12") (pintype "bidirectional"))
      (node (ref "U1A") (pin "18") (pinfunction "VSS@18_18") (pintype "bidirectional"))
      (node (ref "U1A") (pin "31") (pinfunction "VSS@31_31") (pintype "bidirectional"))
      (node (ref "U1A") (pin "47") (pinfunction "VSS@47_47") (pintype "bidirectional"))
      (node (ref "U1A") (pin "63") (pinfunction "VSS@63_63") (pintype "bidirectional"))
    )
    (net (code "72") (name "Net-(BZ1-P)") (class "Default")
      (node (ref "BZ1") (pin "1") (pinfunction "P_1") (pintype "passive"))
      (node (ref "U1A") (pin "61") (pinfunction "PB8_61") (pintype "bidirectional"))
    )
    (net (code "73") (name "Net-(C2-OUTPUT)") (class "Default")
      (node (ref "C2") (pin "3") (pinfunction "OUTPUT_3") (pintype "passive"))
      (node (ref "U1A") (pin "1") (pinfunction "VBAT_1") (pintype "bidirectional"))
    )
    (net (code "74") (name "Net-(D15-PadC)") (class "Default")
      (node (ref "D15") (pin "C") (pinfunction "C_C") (pintype "passive"))
      (node (ref "R81") (pin "2") (pinfunction "2_2") (pintype "passive"))
    )
    (net (code "75") (name "Net-(U1A-BOOT0)") (class "Default")
      (node (ref "B2") (pin "1") (pinfunction "1_1") (pintype "passive"))
      (node (ref "B2") (pin "2") (pinfunction "2_2") (pintype "passive"))
      (node (ref "D10") (pin "C") (pinfunction "C_C") (pintype "passive"))
      (node (ref "R16") (pin "2") (pinfunction "2_2") (pintype "passive"))
      (node (ref "U1A") (pin "60") (pinfunction "BOOT0_60") (pintype "bidirectional"))
    )
    (net (code "76") (name "Net-(U1A-PA2)") (class "Default")
      (node (ref "R56") (pin "2") (pinfunction "2_2") (pintype "passive"))
      (node (ref "U1A") (pin "16") (pinfunction "PA2_16") (pintype "bidirectional"))
    )
    (net (code "77") (name "Net-(U1A-PA3)") (class "Default")
      (node (ref "R57") (pin "2") (pinfunction "2_2") (pintype "passive"))
      (node (ref "U1A") (pin "17") (pinfunction "PA3_17") (pintype "bidirectional"))
    )
    (net (code "78") (name "Net-(U1A-PA4)") (class "Default")
      (node (ref "R7") (pin "2") (pinfunction "2_2") (pintype "passive"))
      (node (ref "U1A") (pin "20") (pinfunction "PA4_20") (pintype "power_in"))
    )
    (net (code "79") (name "Net-(U1A-PA5)") (class "Default")
      (node (ref "R8") (pin "2") (pinfunction "2_2") (pintype "passive"))
      (node (ref "U1A") (pin "21") (pinfunction "PA5_21") (pintype "bidirectional"))
    )
    (net (code "80") (name "Net-(U1A-PA6)") (class "Default")
      (node (ref "R9") (pin "2") (pinfunction "2_2") (pintype "passive"))
      (node (ref "U1A") (pin "22") (pinfunction "PA6_22") (pintype "bidirectional"))
    )
    (net (code "81") (name "Net-(U1A-PA7)") (class "Default")
      (node (ref "R11") (pin "2") (pinfunction "2_2") (pintype "passive"))
      (node (ref "U1A") (pin "23") (pinfunction "PA7_23") (pintype "input"))
    )
    (net (code "82") (name "Net-(U1A-PA9)") (class "Default")
      (node (ref "R12") (pin "2") (pinfunction "2_2") (pintype "passive"))
      (node (ref "U1A") (pin "42") (pinfunction "PA9_42") (pintype "bidirectional"))
    )
    (net (code "83") (name "Net-(U1A-PA10)") (class "Default")
      (node (ref "R13") (pin "2") (pinfunction "2_2") (pintype "passive"))
      (node (ref "U1A") (pin "43") (pinfunction "PA10_43") (pintype "bidirectional"))
    )
    (net (code "84") (name "Net-(U1A-PB0)") (class "Default")
      (node (ref "R91") (pin "2") (pinfunction "2_2") (pintype "passive"))
      (node (ref "U1A") (pin "26") (pinfunction "PB0_26") (pintype "power_in"))
    )
    (net (code "85") (name "Net-(U1A-PB5)") (class "Default")
      (node (ref "R43") (pin "2") (pinfunction "2_2") (pintype "passive"))
      (node (ref "U1A") (pin "57") (pinfunction "PB5_57") (pintype "passive"))
    )
    (net (code "86") (name "Net-(U1A-PB10)") (class "Default")
      (node (ref "R92") (pin "2") (pinfunction "2_2") (pintype "passive"))
      (node (ref "U1A") (pin "29") (pinfunction "PB10_29") (pintype "bidirectional"))
    )
    (net (code "87") (name "Net-(U1A-PB11)") (class "Default")
      (node (ref "R93") (pin "2") (pinfunction "2_2") (pintype "passive"))
      (node (ref "U1A") (pin "30") (pinfunction "PB11_30") (pintype "bidirectional"))
    )
    (net (code "88") (name "Net-(U1A-PC4)") (class "Default")
      (node (ref "R58") (pin "1") (pinfunction "1_1") (pintype "passive"))
      (node (ref "U1A") (pin "24") (pinfunction "PC4_24") (pintype "output"))
    )
    (net (code "89") (name "Net-(U1A-PC5)") (class "Default")
      (node (ref "R90") (pin "1") (pinfunction "1_1") (pintype "passive"))
      (node (ref "U1A") (pin "25") (pinfunction "PC5_25") (pintype "power_in"))
    )
    (net (code "90") (name "Net-(U1A-PC7)") (class "Default")
      (node (ref "R38") (pin "1") (pinfunction "1_1") (pintype "passive"))
      (node (ref "U1A") (pin "38") (pinfunction "PC7_38") (pintype "power_in"))
    )
    (net (code "91") (name "Net-(U1A-PC8)") (class "Default")
      (node (ref "R39") (pin "1") (pinfunction "1_1") (pintype "passive"))
      (node (ref "U1A") (pin "39") (pinfunction "PC8_39") (pintype "bidirectional"))
    )
    (net (code "92") (name "Net-(U1A-PC9)") (class "Default")
      (node (ref "R40") (pin "1") (pinfunction "1_1") (pintype "passive"))
      (node (ref "U1A") (pin "40") (pinfunction "PC9_40") (pintype "bidirectional"))
    )
    (net (code "93") (name "VDDA") (class "Default")
      (node (ref "C26") (pin "2") (pinfunction "2_2") (pintype "passive"))
      (node (ref "C8") (pin "3") (pinfunction "OUTPUT_3") (pintype "passive"))
      (node (ref "U1A") (pin "13") (pinfunction "VDDA/VREF+_13") (pintype "bidirectional"))
    )
    (net (code "94") (name "unconnected-(U1A-PA11-Pad44)") (class "Default")
      (node (ref "U1A") (pin "44") (pinfunction "PA11_44") (pintype "bidirectional+no_connect"))
    )
    (net (code "95") (name "unconnected-(U1A-PA12-Pad45)") (class "Default")
      (node (ref "U1A") (pin "45") (pinfunction "PA12_45") (pintype "bidirectional+no_connect"))
    )
    (net (code "96") (name "unconnected-(U1A-PB6-Pad58)") (class "Default")
      (node (ref "U1A") (pin "58") (pinfunction "PB6_58") (pintype "bidirectional+no_connect"))
    )
    (net (code "97") (name "unconnected-(U1A-PB7-Pad59)") (class "Default")
      (node (ref "U1A") (pin "59") (pinfunction "PB7_59") (pintype "bidirectional+no_connect"))
    )
    (net (code "98") (name "unconnected-(U1A-PB9-Pad62)") (class "Default")
      (node (ref "U1A") (pin "62") (pinfunction "PB9_62") (pintype "bidirectional+no_connect"))
    )
    (net (code "99") (name "unconnected-(U1A-PC0-Pad8)") (class "Default")
      (node (ref "U1A") (pin "8") (pinfunction "PC0_8") (pintype "bidirectional+no_connect"))
    )
    (net (code "100") (name "unconnected-(U1A-PC1-Pad9)") (class "Default")
      (node (ref "U1A") (pin "9") (pinfunction "PC1_9") (pintype "power_in+no_connect"))
    )
    (net (code "101") (name "unconnected-(U1A-PC2-Pad10)") (class "Default")
      (node (ref "U1A") (pin "10") (pinfunction "PC2_10") (pintype "power_in+no_connect"))
    )
    (net (code "102") (name "unconnected-(U1A-PC3-Pad11)") (class "Default")
      (node (ref "U1A") (pin "11") (pinfunction "PC3_11") (pintype "bidirectional+no_connect"))
    )
    (net (code "103") (name "unconnected-(U1A-PC13-Pad2)") (class "Default")
      (node (ref "U1A") (pin "2") (pinfunction "PC13_2") (pintype "bidirectional+no_connect"))
    )
    (net (code "104") (name "unconnected-(U1A-PH0-OSC_IN(PH0)-Pad5)") (class "Default")
      (node (ref "U1A") (pin "5") (pinfunction "PH0-OSC_IN(PH0)_5") (pintype "bidirectional+no_connect"))
    )
    (net (code "105") (name "unconnected-(U1A-PH1-OSC_OUT(PH1)-Pad6)") (class "Default")
      (node (ref "U1A") (pin "6") (pinfunction "PH1-OSC_OUT(PH1)_6") (pintype "bidirectional+no_connect"))
    )
  )
)
